# Clock_Thru.net
KiCad netlist of a schematic drawn in Altium Designer
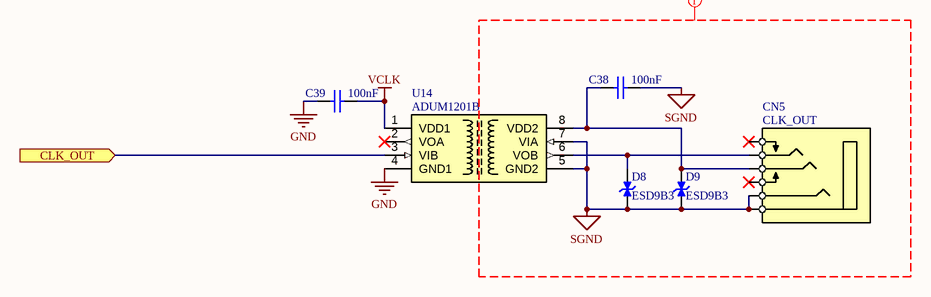
[diagram p0: Clock Thru.SchDoc]

(export (version "E")
  (design (tool "Eeschema 10.0.6"))
  (components
    (comp (ref "C38")
      (value "100nF")
      (footprint "CAP_CHIP_0603")
      (description "0603 Multilayer Ceramic Capacitors MLCC")
      (fields (field (name "TOLERANCE") "10%") (field (name "PARTNUMBER") "CC0603KRX7R9BB104"))
      (libsource (lib "Sainsbury Wellcome Centre") (part "Cap"))
    )
    (comp (ref "C39")
      (value "100nF")
      (footprint "CAP_CHIP_0603")
      (description "0603 Multilayer Ceramic Capacitors MLCC")
      (fields (field (name "TOLERANCE") "10%") (field (name "PARTNUMBER") "CC0603KRX7R9BB104"))
      (libsource (lib "Sainsbury Wellcome Centre") (part "Cap"))
    )
    (comp (ref "CN5")
      (value "CLK_OUT")
      (footprint "PJ-316A")
      (description "3.5mm headphone jack 235℃ 30V 500mA SMD Audio Connector")
      (fields (field (name "PARTNUMBER") "PJ-316A-6A"))
      (libsource (lib "Sainsbury Wellcome Centre") (part "PJ-316A"))
    )
    (comp (ref "D8")
      (value "ESD9B3")
      (footprint "SOD923")
      (description "ESD9B3.3ST5G, Bi-Directional TVS Diode, 300mW, 2-Pin SOD-923")
      (fields (field (name "PARTNUMBER") "ESD9B3.3ST5G"))
      (libsource (lib "Sainsbury Wellcome Centre") (part "TVS-2P-BI"))
    )
    (comp (ref "D9")
      (value "ESD9B3")
      (footprint "SOD923")
      (description "ESD9B3.3ST5G, Bi-Directional TVS Diode, 300mW, 2-Pin SOD-923")
      (fields (field (name "PARTNUMBER") "ESD9B3.3ST5G"))
      (libsource (lib "Sainsbury Wellcome Centre") (part "TVS-2P-BI"))
    )
    (comp (ref "U14")
      (value "ADUM1201B")
      (footprint "SOIC8")
      (description "General Purpose Digital Isolator 2500Vrms 2 Channel 10Mbps 25kV/µs CMTI 8-SOIC (0.154")
      (fields (field (name "PARTNUMBER") "ADUM1201BRZ-RL7"))
      (libsource (lib "Sainsbury Wellcome Centre") (part "ADUM1201"))
    )
  )
  (nets
    (net (code "1") (name "/CLK_OUT") (class "Default")
      (node (ref "U14") (pin "3") (pinfunction "VIB_3") (pintype "input"))
    )
    (net (code "2") (name "GND") (class "Default")
      (node (ref "C39") (pin "2") (pinfunction "2_2") (pintype "passive"))
      (node (ref "U14") (pin "4") (pinfunction "GND1_4") (pintype "power_in"))
    )
    (net (code "3") (name "Net-(CN5-R)") (class "Default")
      (node (ref "C38") (pin "2") (pinfunction "2_2") (pintype "passive"))
      (node (ref "CN5") (pin "3") (pinfunction "R_3") (pintype "passive"))
      (node (ref "D9") (pin "2") (pinfunction "A_2") (pintype "passive"))
      (node (ref "U14") (pin "8") (pinfunction "VDD2_8") (pintype "power_in"))
    )
    (net (code "4") (name "Net-(CN5-T)") (class "Default")
      (node (ref "CN5") (pin "2") (pinfunction "T_2") (pintype "passive"))
      (node (ref "D8") (pin "2") (pinfunction "A_2") (pintype "passive"))
      (node (ref "U14") (pin "6") (pinfunction "VOB_6") (pintype "output"))
    )
    (net (code "5") (name "SGND") (class "Default")
      (node (ref "C38") (pin "1") (pinfunction "1_1") (pintype "passive"))
      (node (ref "CN5") (pin "1") (pinfunction "S_1") (pintype "passive"))
      (node (ref "CN5") (pin "4") (pinfunction "RR_4") (pintype "passive"))
      (node (ref "D8") (pin "1") (pinfunction "K_1") (pintype "passive"))
      (node (ref "D9") (pin "1") (pinfunction "K_1") (pintype "passive"))
      (node (ref "U14") (pin "5") (pinfunction "GND2_5") (pintype "power_in"))
      (node (ref "U14") (pin "7") (pinfunction "VIA_7") (pintype "input"))
    )
    (net (code "6") (name "VCLK") (class "Default")
      (node (ref "C39") (pin "1") (pinfunction "1_1") (pintype "passive"))
      (node (ref "U14") (pin "1") (pinfunction "VDD1_1") (pintype "power_in"))
    )
    (net (code "7") (name "unconnected-(CN5-RS-Pad6)") (class "Default")
      (node (ref "CN5") (pin "6") (pinfunction "RS_6") (pintype "passive+no_connect"))
    )
    (net (code "8") (name "unconnected-(CN5-TS-Pad5)") (class "Default")
      (node (ref "CN5") (pin "5") (pinfunction "TS_5") (pintype "passive+no_connect"))
    )
    (net (code "9") (name "unconnected-(U14-VOA-Pad2)") (class "Default")
      (node (ref "U14") (pin "2") (pinfunction "VOA_2") (pintype "output+no_connect"))
    )
  )
)
